# SCH___2022-10-18.net
KiCad netlist of a schematic drawn in EasyEDA
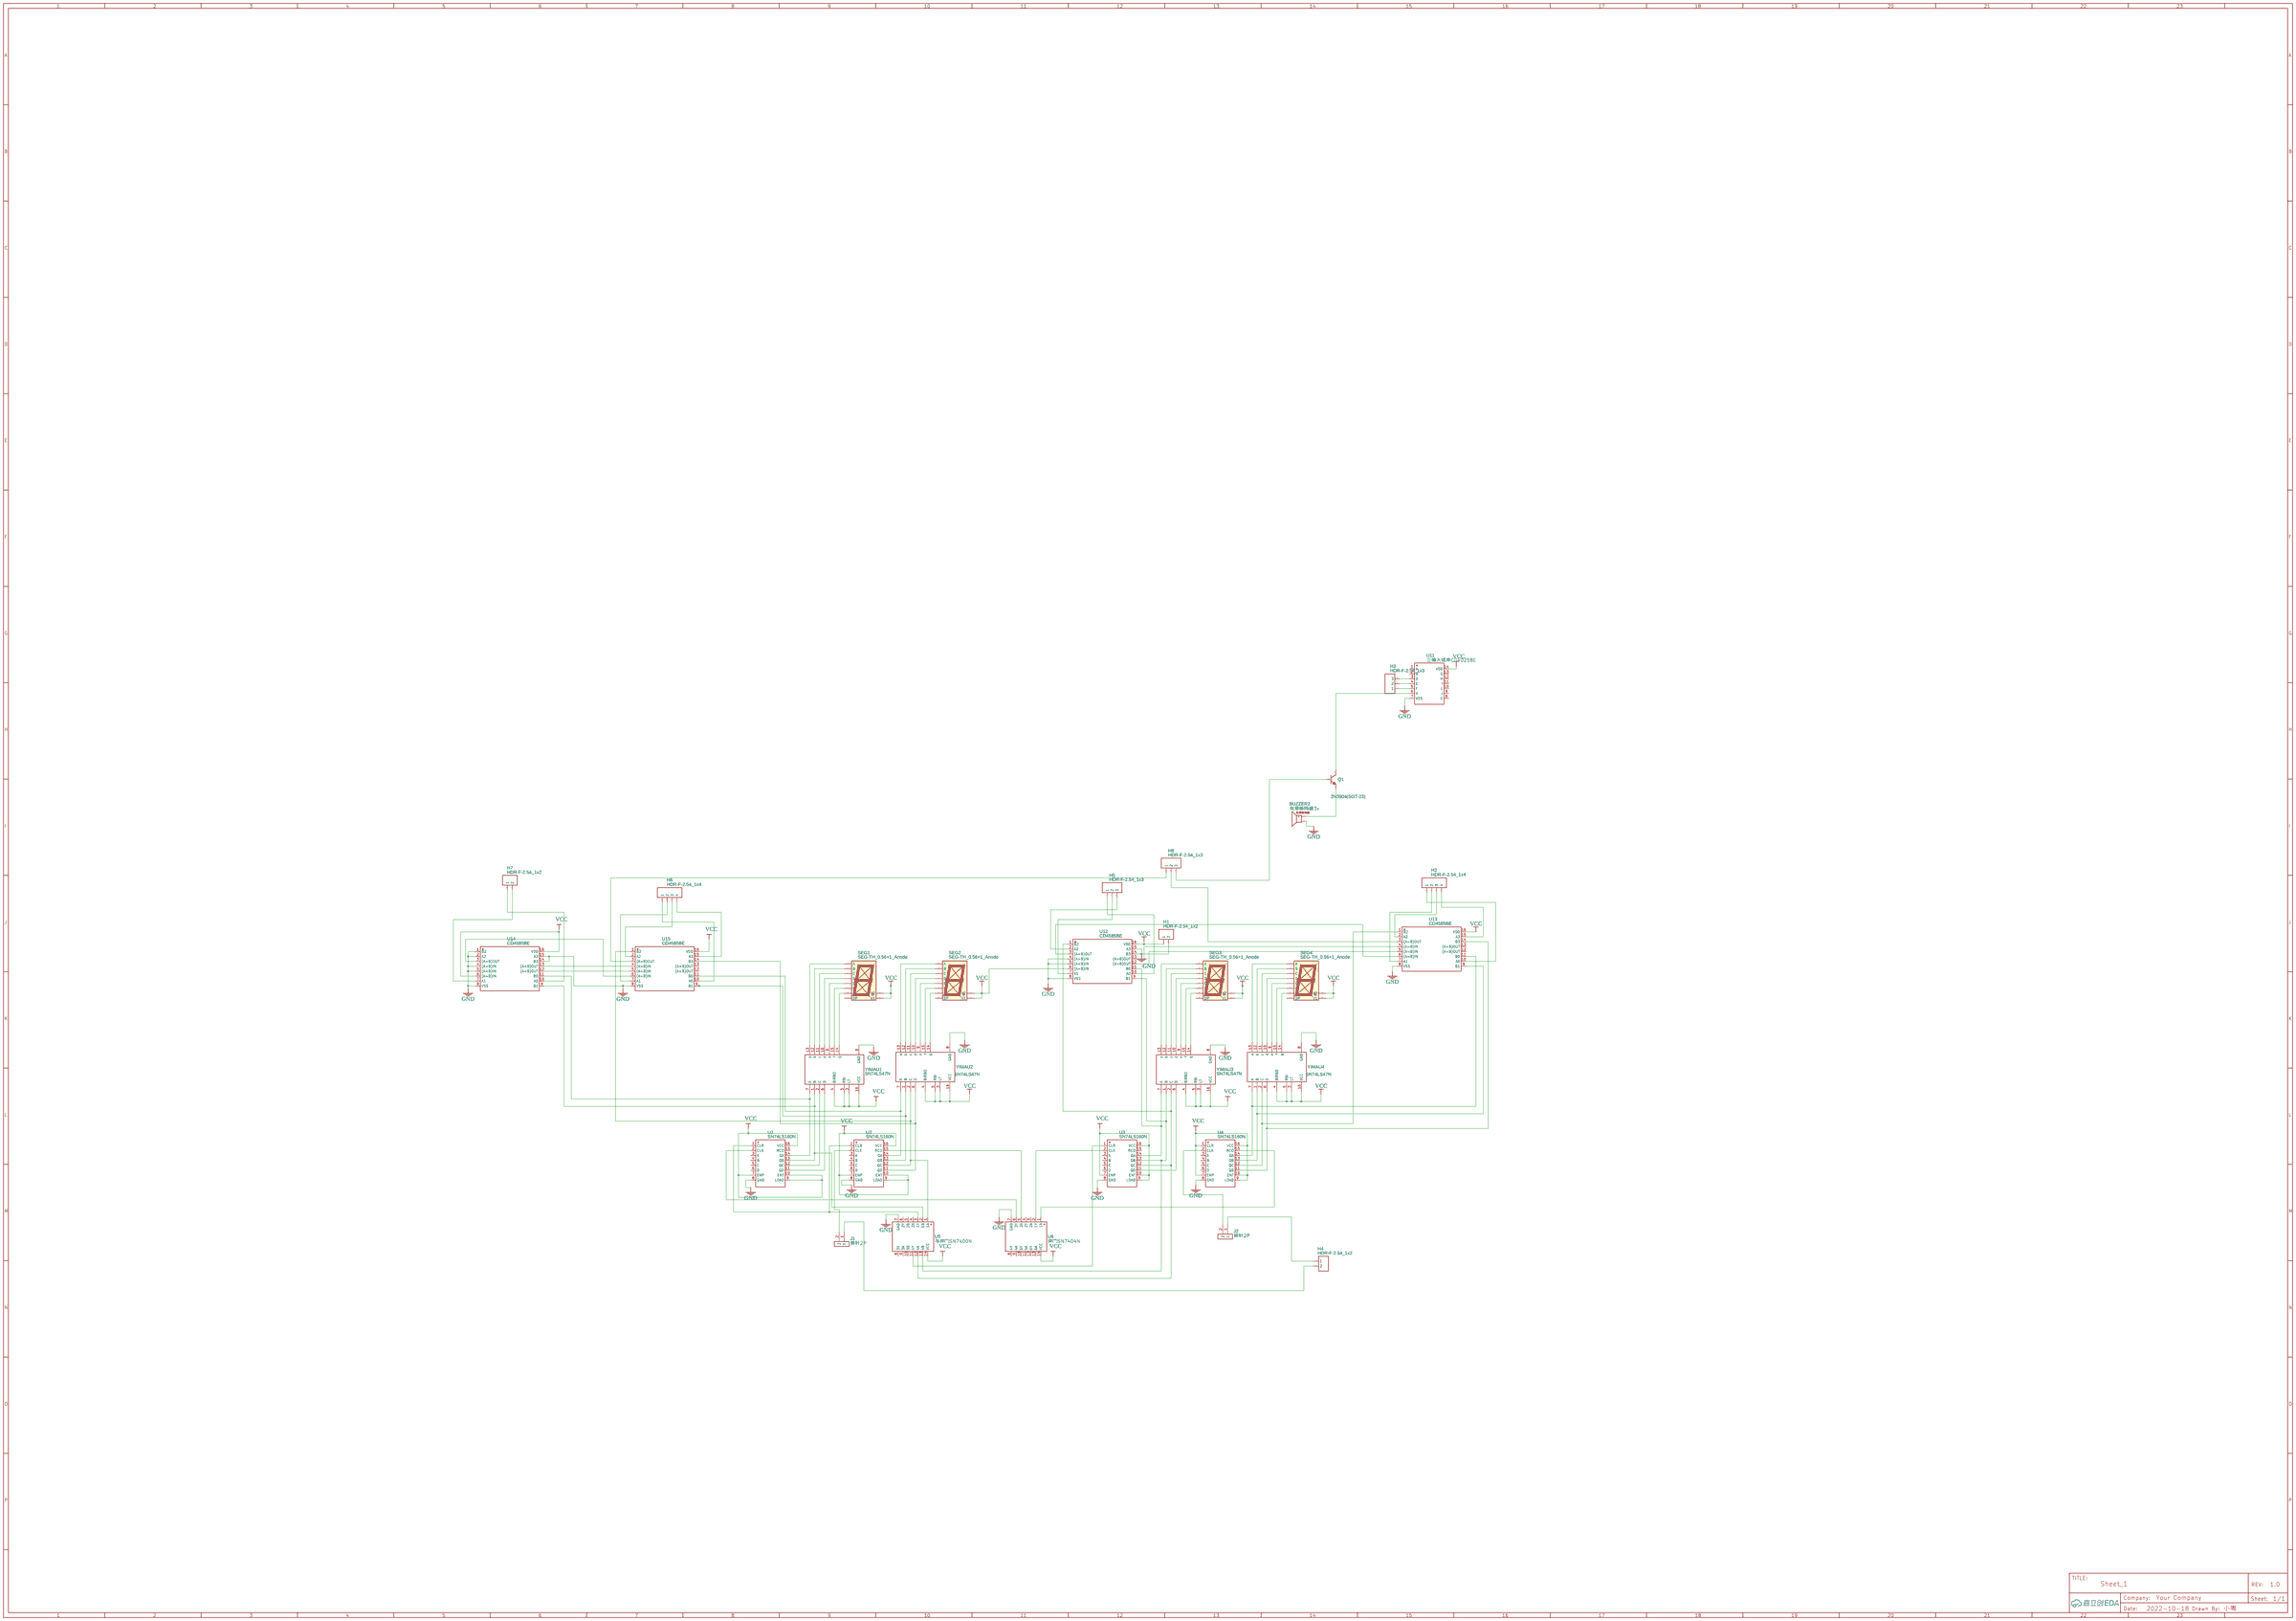
[diagram p0: schematic sheet]

(export (version "E")
  (design (tool "Eeschema 10.0.6"))
  (components
    (comp (ref "BUZZER2")
      (value "有源蜂鸣器3v")
      (fields (field (name "BOM_Manufacturer Part") "TMB12A12") (field (name "BOM_Supplier Part") "C96079"))
      (libsource (lib "") (part "有源蜂鸣器3v"))
    )
    (comp (ref "H1")
      (value "HDR-F-2.54_1x2")
      (fields (field (name "BOM_Supplier Part") "C49661"))
      (libsource (lib "") (part "HDR-F-2.54_1x2"))
    )
    (comp (ref "H2")
      (value "HDR-F-2.54_1x4")
      (fields (field (name "BOM_Supplier Part") "C225501"))
      (libsource (lib "") (part "HDR-F-2.54_1x4"))
    )
    (comp (ref "H3")
      (value "HDR-F-2.54_1x3")
      (fields (field (name "BOM_Supplier Part") "C146690"))
      (libsource (lib "") (part "HDR-F-2.54_1x3_1"))
    )
    (comp (ref "H4")
      (value "HDR-F-2.54_1x2")
      (fields (field (name "BOM_Supplier Part") "C49661"))
      (libsource (lib "") (part "HDR-F-2.54_1x2_1"))
    )
    (comp (ref "H5")
      (value "HDR-F-2.54_1x3")
      (fields (field (name "BOM_Supplier Part") "C146690"))
      (libsource (lib "") (part "HDR-F-2.54_1x3"))
    )
    (comp (ref "H6")
      (value "HDR-F-2.54_1x4")
      (fields (field (name "BOM_Supplier Part") "C225501"))
      (libsource (lib "") (part "HDR-F-2.54_1x4"))
    )
    (comp (ref "H7")
      (value "HDR-F-2.54_1x2")
      (fields (field (name "BOM_Supplier Part") "C49661"))
      (libsource (lib "") (part "HDR-F-2.54_1x2"))
    )
    (comp (ref "H8")
      (value "HDR-F-2.54_1x3")
      (fields (field (name "BOM_Supplier Part") "C146690"))
      (libsource (lib "") (part "HDR-F-2.54_1x3"))
    )
    (comp (ref "J1") (value "排针2P") (libsource (lib "") (part "排针2P")))
    (comp (ref "J2") (value "排针2P") (libsource (lib "") (part "排针2P")))
    (comp (ref "Q1")
      (value "2N3904(SOT-23)")
      (fields
        (field (name "BOM_Manufacturer Part") "2n3904S-RTK/PS")
        (field (name "BOM_Supplier Part") "C18536")
      )
      (libsource (lib "") (part "2N3904(SOT-23)"))
    )
    (comp (ref "SEG1")
      (value "SEG-TH_0.56×1_Anode")
      (fields (field (name "BOM_Supplier Part") "C8092"))
      (libsource (lib "") (part "SEG-TH_0.56×1_Anode"))
    )
    (comp (ref "SEG2")
      (value "SEG-TH_0.56×1_Anode")
      (fields (field (name "BOM_Supplier Part") "C8092"))
      (libsource (lib "") (part "SEG-TH_0.56×1_Anode"))
    )
    (comp (ref "SEG3")
      (value "SEG-TH_0.56×1_Anode")
      (fields (field (name "BOM_Supplier Part") "C8092"))
      (libsource (lib "") (part "SEG-TH_0.56×1_Anode"))
    )
    (comp (ref "SEG4")
      (value "SEG-TH_0.56×1_Anode")
      (fields (field (name "BOM_Supplier Part") "C8092"))
      (libsource (lib "") (part "SEG-TH_0.56×1_Anode"))
    )
    (comp (ref "U1")
      (value "SN74LS160N")
      (fields
        (field (name "BOM_Manufacturer Part") "CC0805JRNPO9BN821")
        (field (name "BOM_Supplier Part") "C113834")
      )
      (libsource (lib "") (part "SN74LS160N"))
    )
    (comp (ref "U2")
      (value "SN74LS160N")
      (fields
        (field (name "BOM_Manufacturer Part") "CC0805JRNPO9BN821")
        (field (name "BOM_Supplier Part") "C113834")
      )
      (libsource (lib "") (part "SN74LS160N"))
    )
    (comp (ref "U3")
      (value "SN74LS160N")
      (fields
        (field (name "BOM_Manufacturer Part") "CC0805JRNPO9BN821")
        (field (name "BOM_Supplier Part") "C113834")
      )
      (libsource (lib "") (part "SN74LS160N"))
    )
    (comp (ref "U4")
      (value "SN74LS160N")
      (fields
        (field (name "BOM_Manufacturer Part") "CC0805JRNPO9BN821")
        (field (name "BOM_Supplier Part") "C113834")
      )
      (libsource (lib "") (part "SN74LS160N"))
    )
    (comp (ref "U5") (value "与非门SN7400N") (libsource (lib "") (part "SN7400N")))
    (comp (ref "U6") (value "非门SN7404N") (libsource (lib "") (part "SN7404N")))
    (comp (ref "U11")
      (value "三输入或非CD4025BE")
      (fields (field (name "BOM_Manufacturer Part") "CD4025BE") (field (name "BOM_Supplier Part") "C28214"))
      (libsource (lib "") (part "CD4025BE"))
    )
    (comp (ref "U12")
      (value "CD4585BE")
      (fields (field (name "BOM_Supplier Part") "C31466"))
      (libsource (lib "") (part "CD4585BE"))
    )
    (comp (ref "U13")
      (value "CD4585BE")
      (fields (field (name "BOM_Supplier Part") "C31466"))
      (libsource (lib "") (part "CD4585BE"))
    )
    (comp (ref "U14")
      (value "CD4585BE")
      (fields (field (name "BOM_Supplier Part") "C31466"))
      (libsource (lib "") (part "CD4585BE"))
    )
    (comp (ref "U15")
      (value "CD4585BE")
      (fields (field (name "BOM_Supplier Part") "C31466"))
      (libsource (lib "") (part "CD4585BE"))
    )
    (comp (ref "YIMAU1")
      (value "SN74LS47N")
      (fields (field (name "BOM_Supplier Part") "C129379"))
      (libsource (lib "") (part "Unknown_1690_-1115"))
    )
    (comp (ref "YIMAU2")
      (value "SN74LS47N")
      (fields (field (name "BOM_Supplier Part") "C129379"))
      (libsource (lib "") (part "Unknown_1875_-1120"))
    )
    (comp (ref "YIMAU3")
      (value "SN74LS47N")
      (fields (field (name "BOM_Supplier Part") "C129379"))
      (libsource (lib "") (part "Unknown_2405_-1115"))
    )
    (comp (ref "YIMAU4")
      (value "SN74LS47N")
      (fields (field (name "BOM_Supplier Part") "C129379"))
      (libsource (lib "") (part "Unknown_2590_-1120"))
    )
  )
  (nets
    (net (code "1") (name "GND") (class "Default")
      (node (ref "BUZZER2") (pin "-") (pinfunction "-_-") (pintype "unspecified"))
      (node (ref "H1") (pin "2") (pinfunction "2_2") (pintype "input"))
      (node (ref "U1") (pin "8") (pinfunction "GND_8") (pintype "unspecified"))
      (node (ref "U11") (pin "7") (pinfunction "VSS_7") (pintype "unspecified"))
      (node (ref "U12") (pin "14") (pinfunction "B3_14") (pintype "unspecified"))
      (node (ref "U12") (pin "15") (pinfunction "A3_15") (pintype "unspecified"))
      (node (ref "U12") (pin "4") (pinfunction "(A>B)IN_4") (pintype "unspecified"))
      (node (ref "U12") (pin "5") (pinfunction "(A<B)IN_5") (pintype "unspecified"))
      (node (ref "U12") (pin "8") (pinfunction "VSS_8") (pintype "unspecified"))
      (node (ref "U13") (pin "8") (pinfunction "VSS_8") (pintype "unspecified"))
      (node (ref "U14") (pin "1") (pinfunction "B2_1") (pintype "unspecified"))
      (node (ref "U14") (pin "14") (pinfunction "B3_14") (pintype "unspecified"))
      (node (ref "U14") (pin "15") (pinfunction "A3_15") (pintype "unspecified"))
      (node (ref "U14") (pin "2") (pinfunction "A2_2") (pintype "unspecified"))
      (node (ref "U14") (pin "4") (pinfunction "(A>B)IN_4") (pintype "unspecified"))
      (node (ref "U14") (pin "5") (pinfunction "(A<B)IN_5") (pintype "unspecified"))
      (node (ref "U14") (pin "8") (pinfunction "VSS_8") (pintype "unspecified"))
      (node (ref "U15") (pin "8") (pinfunction "VSS_8") (pintype "unspecified"))
      (node (ref "U2") (pin "8") (pinfunction "GND_8") (pintype "unspecified"))
      (node (ref "U3") (pin "8") (pinfunction "GND_8") (pintype "unspecified"))
      (node (ref "U4") (pin "8") (pinfunction "GND_8") (pintype "unspecified"))
      (node (ref "U5") (pin "7") (pinfunction "GND_7") (pintype "unspecified"))
      (node (ref "U6") (pin "7") (pinfunction "GND_7") (pintype "unspecified"))
      (node (ref "YIMAU1") (pin "8") (pinfunction "GND_8") (pintype "passive"))
      (node (ref "YIMAU2") (pin "8") (pinfunction "GND_8") (pintype "passive"))
      (node (ref "YIMAU3") (pin "8") (pinfunction "GND_8") (pintype "passive"))
      (node (ref "YIMAU4") (pin "8") (pinfunction "GND_8") (pintype "passive"))
    )
    (net (code "2") (name "Net-(H4-Pad1)") (class "Default")
      (node (ref "H4") (pin "1") (pinfunction "1_1") (pintype "input"))
      (node (ref "J2") (pin "1") (pinfunction "1_1") (pintype "unspecified"))
    )
    (net (code "3") (name "Net-(H4-Pad2)") (class "Default")
      (node (ref "H4") (pin "2") (pinfunction "2_2") (pintype "input"))
      (node (ref "J1") (pin "1") (pinfunction "1_1") (pintype "unspecified"))
    )
    (net (code "4") (name "Net-(Q1-B)") (class "Default")
      (node (ref "H8") (pin "3") (pinfunction "3_3") (pintype "input"))
      (node (ref "Q1") (pin "2") (pinfunction "B_2") (pintype "input"))
    )
    (net (code "5") (name "Net-(Q1-C)") (class "Default")
      (node (ref "Q1") (pin "3") (pinfunction "C_3") (pintype "input"))
      (node (ref "U11") (pin "6") (pinfunction "K_6") (pintype "unspecified"))
    )
    (net (code "6") (name "Net-(Q1-E)") (class "Default")
      (node (ref "BUZZER2") (pin "+") (pinfunction "+_+") (pintype "unspecified"))
      (node (ref "Q1") (pin "1") (pinfunction "E_1") (pintype "input"))
    )
    (net (code "7") (name "Net-(SEG1-A)") (class "Default")
      (node (ref "SEG1") (pin "7") (pinfunction "A_7") (pintype "unspecified"))
      (node (ref "YIMAU1") (pin "13") (pinfunction "a_13") (pintype "unspecified"))
    )
    (net (code "8") (name "Net-(SEG1-B)") (class "Default")
      (node (ref "SEG1") (pin "6") (pinfunction "B_6") (pintype "unspecified"))
      (node (ref "YIMAU1") (pin "12") (pinfunction "b_12") (pintype "unspecified"))
    )
    (net (code "9") (name "Net-(SEG1-C)") (class "Default")
      (node (ref "SEG1") (pin "4") (pinfunction "C_4") (pintype "unspecified"))
      (node (ref "YIMAU1") (pin "11") (pinfunction "c_11") (pintype "unspecified"))
    )
    (net (code "10") (name "Net-(SEG1-D)") (class "Default")
      (node (ref "SEG1") (pin "2") (pinfunction "D_2") (pintype "unspecified"))
      (node (ref "YIMAU1") (pin "10") (pinfunction "d_10") (pintype "unspecified"))
    )
    (net (code "11") (name "Net-(SEG1-E)") (class "Default")
      (node (ref "SEG1") (pin "1") (pinfunction "E_1") (pintype "unspecified"))
      (node (ref "YIMAU1") (pin "9") (pinfunction "e_9") (pintype "unspecified"))
    )
    (net (code "12") (name "Net-(SEG1-F)") (class "Default")
      (node (ref "SEG1") (pin "9") (pinfunction "F_9") (pintype "unspecified"))
      (node (ref "YIMAU1") (pin "15") (pinfunction "f_15") (pintype "unspecified"))
    )
    (net (code "13") (name "Net-(SEG1-G)") (class "Default")
      (node (ref "SEG1") (pin "10") (pinfunction "G_10") (pintype "unspecified"))
      (node (ref "YIMAU1") (pin "14") (pinfunction "g_14") (pintype "unspecified"))
    )
    (net (code "14") (name "Net-(SEG2-A)") (class "Default")
      (node (ref "SEG2") (pin "7") (pinfunction "A_7") (pintype "unspecified"))
      (node (ref "YIMAU2") (pin "13") (pinfunction "a_13") (pintype "unspecified"))
    )
    (net (code "15") (name "Net-(SEG2-B)") (class "Default")
      (node (ref "SEG2") (pin "6") (pinfunction "B_6") (pintype "unspecified"))
      (node (ref "YIMAU2") (pin "12") (pinfunction "b_12") (pintype "unspecified"))
    )
    (net (code "16") (name "Net-(SEG2-C)") (class "Default")
      (node (ref "SEG2") (pin "4") (pinfunction "C_4") (pintype "unspecified"))
      (node (ref "YIMAU2") (pin "11") (pinfunction "c_11") (pintype "unspecified"))
    )
    (net (code "17") (name "Net-(SEG2-D)") (class "Default")
      (node (ref "SEG2") (pin "2") (pinfunction "D_2") (pintype "unspecified"))
      (node (ref "YIMAU2") (pin "10") (pinfunction "d_10") (pintype "unspecified"))
    )
    (net (code "18") (name "Net-(SEG2-E)") (class "Default")
      (node (ref "SEG2") (pin "1") (pinfunction "E_1") (pintype "unspecified"))
      (node (ref "YIMAU2") (pin "9") (pinfunction "e_9") (pintype "unspecified"))
    )
    (net (code "19") (name "Net-(SEG2-F)") (class "Default")
      (node (ref "SEG2") (pin "9") (pinfunction "F_9") (pintype "unspecified"))
      (node (ref "YIMAU2") (pin "15") (pinfunction "f_15") (pintype "unspecified"))
    )
    (net (code "20") (name "Net-(SEG2-G)") (class "Default")
      (node (ref "SEG2") (pin "10") (pinfunction "G_10") (pintype "unspecified"))
      (node (ref "YIMAU2") (pin "14") (pinfunction "g_14") (pintype "unspecified"))
    )
    (net (code "21") (name "Net-(SEG3-A)") (class "Default")
      (node (ref "SEG3") (pin "7") (pinfunction "A_7") (pintype "unspecified"))
      (node (ref "YIMAU3") (pin "13") (pinfunction "a_13") (pintype "unspecified"))
    )
    (net (code "22") (name "Net-(SEG3-B)") (class "Default")
      (node (ref "SEG3") (pin "6") (pinfunction "B_6") (pintype "unspecified"))
      (node (ref "YIMAU3") (pin "12") (pinfunction "b_12") (pintype "unspecified"))
    )
    (net (code "23") (name "Net-(SEG3-C)") (class "Default")
      (node (ref "SEG3") (pin "4") (pinfunction "C_4") (pintype "unspecified"))
      (node (ref "YIMAU3") (pin "11") (pinfunction "c_11") (pintype "unspecified"))
    )
    (net (code "24") (name "Net-(SEG3-D)") (class "Default")
      (node (ref "SEG3") (pin "2") (pinfunction "D_2") (pintype "unspecified"))
      (node (ref "YIMAU3") (pin "10") (pinfunction "d_10") (pintype "unspecified"))
    )
    (net (code "25") (name "Net-(SEG3-E)") (class "Default")
      (node (ref "SEG3") (pin "1") (pinfunction "E_1") (pintype "unspecified"))
      (node (ref "YIMAU3") (pin "9") (pinfunction "e_9") (pintype "unspecified"))
    )
    (net (code "26") (name "Net-(SEG3-F)") (class "Default")
      (node (ref "SEG3") (pin "9") (pinfunction "F_9") (pintype "unspecified"))
      (node (ref "YIMAU3") (pin "15") (pinfunction "f_15") (pintype "unspecified"))
    )
    (net (code "27") (name "Net-(SEG3-G)") (class "Default")
      (node (ref "SEG3") (pin "10") (pinfunction "G_10") (pintype "unspecified"))
      (node (ref "YIMAU3") (pin "14") (pinfunction "g_14") (pintype "unspecified"))
    )
    (net (code "28") (name "Net-(SEG4-A)") (class "Default")
      (node (ref "SEG4") (pin "7") (pinfunction "A_7") (pintype "unspecified"))
      (node (ref "YIMAU4") (pin "13") (pinfunction "a_13") (pintype "unspecified"))
    )
    (net (code "29") (name "Net-(SEG4-B)") (class "Default")
      (node (ref "SEG4") (pin "6") (pinfunction "B_6") (pintype "unspecified"))
      (node (ref "YIMAU4") (pin "12") (pinfunction "b_12") (pintype "unspecified"))
    )
    (net (code "30") (name "Net-(SEG4-C)") (class "Default")
      (node (ref "SEG4") (pin "4") (pinfunction "C_4") (pintype "unspecified"))
      (node (ref "YIMAU4") (pin "11") (pinfunction "c_11") (pintype "unspecified"))
    )
    (net (code "31") (name "Net-(SEG4-D)") (class "Default")
      (node (ref "SEG4") (pin "2") (pinfunction "D_2") (pintype "unspecified"))
      (node (ref "YIMAU4") (pin "10") (pinfunction "d_10") (pintype "unspecified"))
    )
    (net (code "32") (name "Net-(SEG4-E)") (class "Default")
      (node (ref "SEG4") (pin "1") (pinfunction "E_1") (pintype "unspecified"))
      (node (ref "YIMAU4") (pin "9") (pinfunction "e_9") (pintype "unspecified"))
    )
    (net (code "33") (name "Net-(SEG4-F)") (class "Default")
      (node (ref "SEG4") (pin "9") (pinfunction "F_9") (pintype "unspecified"))
      (node (ref "YIMAU4") (pin "15") (pinfunction "f_15") (pintype "unspecified"))
    )
    (net (code "34") (name "Net-(SEG4-G)") (class "Default")
      (node (ref "SEG4") (pin "10") (pinfunction "G_10") (pintype "unspecified"))
      (node (ref "YIMAU4") (pin "14") (pinfunction "g_14") (pintype "unspecified"))
    )
    (net (code "35") (name "Net-(U1-CLK)") (class "Default")
      (node (ref "U1") (pin "2") (pinfunction "CLK_2") (pintype "unspecified"))
      (node (ref "U6") (pin "6") (pinfunction "3Y_6") (pintype "unspecified"))
    )
    (net (code "36") (name "Net-(U1-CLR)") (class "Default")
      (node (ref "U1") (pin "1") (pinfunction "CLR_1") (pintype "unspecified"))
      (node (ref "U2") (pin "1") (pinfunction "CLR_1") (pintype "unspecified"))
      (node (ref "U5") (pin "3") (pinfunction "1Y_3") (pintype "unspecified"))
    )
    (net (code "37") (name "Net-(U1-QA)") (class "Default")
      (node (ref "U1") (pin "14") (pinfunction "QA_14") (pintype "unspecified"))
      (node (ref "U14") (pin "11") (pinfunction "B0_11") (pintype "unspecified"))
      (node (ref "YIMAU1") (pin "7") (pinfunction "A_7") (pintype "unspecified"))
    )
    (net (code "38") (name "Net-(U1-QB)") (class "Default")
      (node (ref "U1") (pin "13") (pinfunction "QB_13") (pintype "unspecified"))
      (node (ref "U14") (pin "9") (pinfunction "B1_9") (pintype "unspecified"))
      (node (ref "U5") (pin "2") (pinfunction "1B_2") (pintype "unspecified"))
      (node (ref "YIMAU1") (pin "1") (pinfunction "B_1") (pintype "unspecified"))
    )
    (net (code "39") (name "Net-(U1-QC)") (class "Default")
      (node (ref "U1") (pin "12") (pinfunction "QC_12") (pintype "unspecified"))
      (node (ref "YIMAU1") (pin "2") (pinfunction "C_2") (pintype "unspecified"))
    )
    (net (code "40") (name "Net-(U1-QD)") (class "Default")
      (node (ref "U1") (pin "11") (pinfunction "QD_11") (pintype "unspecified"))
      (node (ref "YIMAU1") (pin "6") (pinfunction "D_6") (pintype "unspecified"))
    )
    (net (code "41") (name "Net-(U2-CLK)") (class "Default")
      (node (ref "J1") (pin "2") (pinfunction "2_2") (pintype "unspecified"))
      (node (ref "U2") (pin "2") (pinfunction "CLK_2") (pintype "unspecified"))
    )
    (net (code "42") (name "Net-(U2-RCO)") (class "Default")
      (node (ref "U2") (pin "15") (pinfunction "RCO_15") (pintype "unspecified"))
      (node (ref "U6") (pin "5") (pinfunction "3A_5") (pintype "unspecified"))
    )
    (net (code "43") (name "Net-(U3-CLK)") (class "Default")
      (node (ref "U3") (pin "2") (pinfunction "CLK_2") (pintype "unspecified"))
      (node (ref "U6") (pin "2") (pinfunction "1Y_2") (pintype "unspecified"))
    )
    (net (code "44") (name "Net-(U3-CLR)") (class "Default")
      (node (ref "U3") (pin "1") (pinfunction "CLR_1") (pintype "unspecified"))
      (node (ref "U5") (pin "11") (pinfunction "4Y_11") (pintype "unspecified"))
    )
    (net (code "45") (name "Net-(U3-QD)") (class "Default")
      (node (ref "U3") (pin "11") (pinfunction "QD_11") (pintype "unspecified"))
      (node (ref "YIMAU3") (pin "6") (pinfunction "D_6") (pintype "unspecified"))
    )
    (net (code "46") (name "Net-(U4-CLK)") (class "Default")
      (node (ref "J2") (pin "2") (pinfunction "2_2") (pintype "unspecified"))
      (node (ref "U4") (pin "2") (pinfunction "CLK_2") (pintype "unspecified"))
    )
    (net (code "47") (name "Net-(U4-RCO)") (class "Default")
      (node (ref "U4") (pin "15") (pinfunction "RCO_15") (pintype "unspecified"))
      (node (ref "U6") (pin "1") (pinfunction "1A_1") (pintype "unspecified"))
    )
    (net (code "48") (name "Net-(U11-D)") (class "Default")
      (node (ref "H3") (pin "3") (pinfunction "3_3") (pintype "input"))
      (node (ref "U11") (pin "3") (pinfunction "D_3") (pintype "unspecified"))
    )
    (net (code "49") (name "Net-(U11-E)") (class "Default")
      (node (ref "H3") (pin "2") (pinfunction "2_2") (pintype "input"))
      (node (ref "U11") (pin "4") (pinfunction "E_4") (pintype "unspecified"))
    )
    (net (code "50") (name "Net-(U11-F)") (class "Default")
      (node (ref "H3") (pin "1") (pinfunction "1_1") (pintype "input"))
      (node (ref "U11") (pin "5") (pinfunction "F_5") (pintype "unspecified"))
    )
    (net (code "51") (name "Net-(U12-(A<B)OUT)") (class "Default")
      (node (ref "U12") (pin "12") (pinfunction "(A<B)OUT_12") (pintype "unspecified"))
      (node (ref "U13") (pin "5") (pinfunction "(A<B)IN_5") (pintype "unspecified"))
    )
    (net (code "52") (name "Net-(U12-(A=B)OUT)") (class "Default")
      (node (ref "U12") (pin "3") (pinfunction "(A=B)OUT_3") (pintype "unspecified"))
      (node (ref "U13") (pin "6") (pinfunction "(A=B)IN_6") (pintype "unspecified"))
    )
    (net (code "53") (name "Net-(U12-(A>B)OUT)") (class "Default")
      (node (ref "U12") (pin "13") (pinfunction "(A>B)OUT_13") (pintype "unspecified"))
      (node (ref "U13") (pin "4") (pinfunction "(A>B)IN_4") (pintype "unspecified"))
    )
    (net (code "54") (name "Net-(U12-A0)") (class "Default")
      (node (ref "H5") (pin "1") (pinfunction "1_1") (pintype "input"))
      (node (ref "U12") (pin "10") (pinfunction "A0_10") (pintype "unspecified"))
    )
    (net (code "55") (name "Net-(U12-A1)") (class "Default")
      (node (ref "H5") (pin "2") (pinfunction "2_2") (pintype "input"))
      (node (ref "U12") (pin "7") (pinfunction "A1_7") (pintype "unspecified"))
    )
    (net (code "56") (name "Net-(U12-A2)") (class "Default")
      (node (ref "H5") (pin "3") (pinfunction "3_3") (pintype "input"))
      (node (ref "U12") (pin "2") (pinfunction "A2_2") (pintype "unspecified"))
    )
    (net (code "57") (name "Net-(U12-B0)") (class "Default")
      (node (ref "U12") (pin "11") (pinfunction "B0_11") (pintype "unspecified"))
      (node (ref "U3") (pin "14") (pinfunction "QA_14") (pintype "unspecified"))
      (node (ref "YIMAU3") (pin "7") (pinfunction "A_7") (pintype "unspecified"))
    )
    (net (code "58") (name "Net-(U12-B1)") (class "Default")
      (node (ref "U12") (pin "9") (pinfunction "B1_9") (pintype "unspecified"))
      (node (ref "U3") (pin "13") (pinfunction "QB_13") (pintype "unspecified"))
      (node (ref "U5") (pin "13") (pinfunction "4B_13") (pintype "unspecified"))
      (node (ref "YIMAU3") (pin "1") (pinfunction "B_1") (pintype "unspecified"))
    )
    (net (code "59") (name "Net-(U12-B2)") (class "Default")
      (node (ref "U12") (pin "1") (pinfunction "B2_1") (pintype "unspecified"))
      (node (ref "U3") (pin "12") (pinfunction "QC_12") (pintype "unspecified"))
      (node (ref "U5") (pin "12") (pinfunction "4A_12") (pintype "unspecified"))
      (node (ref "YIMAU3") (pin "2") (pinfunction "C_2") (pintype "unspecified"))
    )
    (net (code "60") (name "Net-(U13-(A=B)OUT)") (class "Default")
      (node (ref "H8") (pin "2") (pinfunction "2_2") (pintype "input"))
      (node (ref "U13") (pin "3") (pinfunction "(A=B)OUT_3") (pintype "unspecified"))
    )
    (net (code "61") (name "Net-(U13-A0)") (class "Default")
      (node (ref "H2") (pin "1") (pinfunction "1_1") (pintype "unspecified"))
      (node (ref "U13") (pin "10") (pinfunction "A0_10") (pintype "unspecified"))
    )
    (net (code "62") (name "Net-(U13-A1)") (class "Default")
      (node (ref "H2") (pin "2") (pinfunction "2_2") (pintype "unspecified"))
      (node (ref "U13") (pin "7") (pinfunction "A1_7") (pintype "unspecified"))
    )
    (net (code "63") (name "Net-(U13-A2)") (class "Default")
      (node (ref "H2") (pin "3") (pinfunction "3_3") (pintype "unspecified"))
      (node (ref "U13") (pin "2") (pinfunction "A2_2") (pintype "unspecified"))
    )
    (net (code "64") (name "Net-(U13-A3)") (class "Default")
      (node (ref "H2") (pin "4") (pinfunction "4_4") (pintype "unspecified"))
      (node (ref "U13") (pin "15") (pinfunction "A3_15") (pintype "unspecified"))
    )
    (net (code "65") (name "Net-(U13-B0)") (class "Default")
      (node (ref "U13") (pin "11") (pinfunction "B0_11") (pintype "unspecified"))
      (node (ref "U4") (pin "14") (pinfunction "QA_14") (pintype "unspecified"))
      (node (ref "YIMAU4") (pin "7") (pinfunction "A_7") (pintype "unspecified"))
    )
    (net (code "66") (name "Net-(U13-B1)") (class "Default")
      (node (ref "U13") (pin "9") (pinfunction "B1_9") (pintype "unspecified"))
      (node (ref "U4") (pin "13") (pinfunction "QB_13") (pintype "unspecified"))
      (node (ref "YIMAU4") (pin "1") (pinfunction "B_1") (pintype "unspecified"))
    )
    (net (code "67") (name "Net-(U13-B2)") (class "Default")
      (node (ref "U13") (pin "1") (pinfunction "B2_1") (pintype "unspecified"))
      (node (ref "U4") (pin "12") (pinfunction "QC_12") (pintype "unspecified"))
      (node (ref "YIMAU4") (pin "2") (pinfunction "C_2") (pintype "unspecified"))
    )
    (net (code "68") (name "Net-(U13-B3)") (class "Default")
      (node (ref "U13") (pin "14") (pinfunction "B3_14") (pintype "unspecified"))
      (node (ref "U4") (pin "11") (pinfunction "QD_11") (pintype "unspecified"))
      (node (ref "YIMAU4") (pin "6") (pinfunction "D_6") (pintype "unspecified"))
    )
    (net (code "69") (name "Net-(U14-(A<B)OUT)") (class "Default")
      (node (ref "U14") (pin "12") (pinfunction "(A<B)OUT_12") (pintype "unspecified"))
      (node (ref "U15") (pin "5") (pinfunction "(A<B)IN_5") (pintype "unspecified"))
    )
    (net (code "70") (name "Net-(U14-(A=B)OUT)") (class "Default")
      (node (ref "U14") (pin "3") (pinfunction "(A=B)OUT_3") (pintype "unspecified"))
      (node (ref "U15") (pin "6") (pinfunction "(A=B)IN_6") (pintype "unspecified"))
    )
    (net (code "71") (name "Net-(U14-(A>B)OUT)") (class "Default")
      (node (ref "U14") (pin "13") (pinfunction "(A>B)OUT_13") (pintype "unspecified"))
      (node (ref "U15") (pin "4") (pinfunction "(A>B)IN_4") (pintype "unspecified"))
    )
    (net (code "72") (name "Net-(U14-A0)") (class "Default")
      (node (ref "H7") (pin "1") (pinfunction "1_1") (pintype "input"))
      (node (ref "U14") (pin "10") (pinfunction "A0_10") (pintype "unspecified"))
    )
    (net (code "73") (name "Net-(U14-A1)") (class "Default")
      (node (ref "H7") (pin "2") (pinfunction "2_2") (pintype "input"))
      (node (ref "U14") (pin "7") (pinfunction "A1_7") (pintype "unspecified"))
    )
    (net (code "74") (name "Net-(U15-(A=B)OUT)") (class "Default")
      (node (ref "H8") (pin "1") (pinfunction "1_1") (pintype "input"))
      (node (ref "U15") (pin "3") (pinfunction "(A=B)OUT_3") (pintype "unspecified"))
    )
    (net (code "75") (name "Net-(U15-A0)") (class "Default")
      (node (ref "H6") (pin "1") (pinfunction "1_1") (pintype "unspecified"))
      (node (ref "U15") (pin "10") (pinfunction "A0_10") (pintype "unspecified"))
    )
    (net (code "76") (name "Net-(U15-A1)") (class "Default")
      (node (ref "H6") (pin "2") (pinfunction "2_2") (pintype "unspecified"))
      (node (ref "U15") (pin "7") (pinfunction "A1_7") (pintype "unspecified"))
    )
    (net (code "77") (name "Net-(U15-A2)") (class "Default")
      (node (ref "H6") (pin "3") (pinfunction "3_3") (pintype "unspecified"))
      (node (ref "U15") (pin "2") (pinfunction "A2_2") (pintype "unspecified"))
    )
    (net (code "78") (name "Net-(U15-A3)") (class "Default")
      (node (ref "H6") (pin "4") (pinfunction "4_4") (pintype "unspecified"))
      (node (ref "U15") (pin "15") (pinfunction "A3_15") (pintype "unspecified"))
    )
    (net (code "79") (name "Net-(U15-B0)") (class "Default")
      (node (ref "U15") (pin "11") (pinfunction "B0_11") (pintype "unspecified"))
      (node (ref "U2") (pin "14") (pinfunction "QA_14") (pintype "unspecified"))
      (node (ref "YIMAU2") (pin "7") (pinfunction "A_7") (pintype "unspecified"))
    )
    (net (code "80") (name "Net-(U15-B1)") (class "Default")
      (node (ref "U15") (pin "9") (pinfunction "B1_9") (pintype "unspecified"))
      (node (ref "U2") (pin "13") (pinfunction "QB_13") (pintype "unspecified"))
      (node (ref "YIMAU2") (pin "1") (pinfunction "B_1") (pintype "unspecified"))
    )
    (net (code "81") (name "Net-(U15-B2)") (class "Default")
      (node (ref "U15") (pin "1") (pinfunction "B2_1") (pintype "unspecified"))
      (node (ref "U2") (pin "12") (pinfunction "QC_12") (pintype "unspecified"))
      (node (ref "U5") (pin "1") (pinfunction "1A_1") (pintype "unspecified"))
      (node (ref "YIMAU2") (pin "2") (pinfunction "C_2") (pintype "unspecified"))
    )
    (net (code "82") (name "Net-(U15-B3)") (class "Default")
      (node (ref "U15") (pin "14") (pinfunction "B3_14") (pintype "unspecified"))
      (node (ref "U2") (pin "11") (pinfunction "QD_11") (pintype "unspecified"))
      (node (ref "YIMAU2") (pin "6") (pinfunction "D_6") (pintype "unspecified"))
    )
    (net (code "83") (name "VCC") (class "Default")
      (node (ref "H1") (pin "1") (pinfunction "1_1") (pintype "input"))
      (node (ref "SEG1") (pin "3") (pinfunction "V1_3") (pintype "unspecified"))
      (node (ref "SEG1") (pin "8") (pinfunction "V2_8") (pintype "unspecified"))
      (node (ref "SEG2") (pin "3") (pinfunction "V1_3") (pintype "unspecified"))
      (node (ref "SEG2") (pin "8") (pinfunction "V2_8") (pintype "unspecified"))
      (node (ref "SEG3") (pin "3") (pinfunction "V1_3") (pintype "unspecified"))
      (node (ref "SEG3") (pin "8") (pinfunction "V2_8") (pintype "unspecified"))
      (node (ref "SEG4") (pin "3") (pinfunction "V1_3") (pintype "unspecified"))
      (node (ref "SEG4") (pin "8") (pinfunction "V2_8") (pintype "unspecified"))
      (node (ref "U1") (pin "10") (pinfunction "ENT_10") (pintype "unspecified"))
      (node (ref "U1") (pin "16") (pinfunction "VCC_16") (pintype "unspecified"))
      (node (ref "U1") (pin "7") (pinfunction "ENP_7") (pintype "unspecified"))
      (node (ref "U1") (pin "9") (pinfunction "LOAD_9") (pintype "unspecified"))
      (node (ref "U11") (pin "14") (pinfunction "VDD_14") (pintype "unspecified"))
      (node (ref "U12") (pin "16") (pinfunction "VDD_16") (pintype "unspecified"))
      (node (ref "U12") (pin "6") (pinfunction "(A=B)IN_6") (pintype "unspecified"))
      (node (ref "U13") (pin "16") (pinfunction "VDD_16") (pintype "unspecified"))
      (node (ref "U14") (pin "16") (pinfunction "VDD_16") (pintype "unspecified"))
      (node (ref "U14") (pin "6") (pinfunction "(A=B)IN_6") (pintype "unspecified"))
      (node (ref "U15") (pin "16") (pinfunction "VDD_16") (pintype "unspecified"))
      (node (ref "U2") (pin "10") (pinfunction "ENT_10") (pintype "unspecified"))
      (node (ref "U2") (pin "16") (pinfunction "VCC_16") (pintype "unspecified"))
      (node (ref "U2") (pin "7") (pinfunction "ENP_7") (pintype "unspecified"))
      (node (ref "U2") (pin "9") (pinfunction "LOAD_9") (pintype "unspecified"))
      (node (ref "U3") (pin "10") (pinfunction "ENT_10") (pintype "unspecified"))
      (node (ref "U3") (pin "16") (pinfunction "VCC_16") (pintype "unspecified"))
      (node (ref "U3") (pin "7") (pinfunction "ENP_7") (pintype "unspecified"))
      (node (ref "U3") (pin "9") (pinfunction "LOAD_9") (pintype "unspecified"))
      (node (ref "U4") (pin "1") (pinfunction "CLR_1") (pintype "unspecified"))
      (node (ref "U4") (pin "10") (pinfunction "ENT_10") (pintype "unspecified"))
      (node (ref "U4") (pin "16") (pinfunction "VCC_16") (pintype "unspecified"))
      (node (ref "U4") (pin "7") (pinfunction "ENP_7") (pintype "unspecified"))
      (node (ref "U4") (pin "9") (pinfunction "LOAD_9") (pintype "unspecified"))
      (node (ref "U5") (pin "14") (pinfunction "VCC_14") (pintype "unspecified"))
      (node (ref "U6") (pin "14") (pinfunction "VCC_14") (pintype "unspecified"))
      (node (ref "YIMAU1") (pin "16") (pinfunction "VCC_16") (pintype "passive"))
      (node (ref "YIMAU1") (pin "3") (pinfunction "LT_3") (pintype "unspecified"))
      (node (ref "YIMAU1") (pin "4") (pinfunction "BIRBO_4") (pintype "bidirectional"))
      (node (ref "YIMAU1") (pin "5") (pinfunction "RBI_5") (pintype "unspecified"))
      (node (ref "YIMAU2") (pin "16") (pinfunction "VCC_16") (pintype "passive"))
      (node (ref "YIMAU2") (pin "3") (pinfunction "LT_3") (pintype "unspecified"))
      (node (ref "YIMAU2") (pin "4") (pinfunction "BIRBO_4") (pintype "bidirectional"))
      (node (ref "YIMAU2") (pin "5") (pinfunction "RBI_5") (pintype "unspecified"))
      (node (ref "YIMAU3") (pin "16") (pinfunction "VCC_16") (pintype "passive"))
      (node (ref "YIMAU3") (pin "3") (pinfunction "LT_3") (pintype "unspecified"))
      (node (ref "YIMAU3") (pin "4") (pinfunction "BIRBO_4") (pintype "bidirectional"))
      (node (ref "YIMAU3") (pin "5") (pinfunction "RBI_5") (pintype "unspecified"))
      (node (ref "YIMAU4") (pin "16") (pinfunction "VCC_16") (pintype "passive"))
      (node (ref "YIMAU4") (pin "3") (pinfunction "LT_3") (pintype "unspecified"))
      (node (ref "YIMAU4") (pin "4") (pinfunction "BIRBO_4") (pintype "bidirectional"))
      (node (ref "YIMAU4") (pin "5") (pinfunction "RBI_5") (pintype "unspecified"))
    )
    (net (code "84") (name "unconnected-(SEG1-DP-Pad5)") (class "Default")
      (node (ref "SEG1") (pin "5") (pinfunction "DP_5") (pintype "unspecified"))
    )
    (net (code "85") (name "unconnected-(SEG2-DP-Pad5)") (class "Default")
      (node (ref "SEG2") (pin "5") (pinfunction "DP_5") (pintype "unspecified"))
    )
    (net (code "86") (name "unconnected-(SEG3-DP-Pad5)") (class "Default")
      (node (ref "SEG3") (pin "5") (pinfunction "DP_5") (pintype "unspecified"))
    )
    (net (code "87") (name "unconnected-(SEG4-DP-Pad5)") (class "Default")
      (node (ref "SEG4") (pin "5") (pinfunction "DP_5") (pintype "unspecified"))
    )
    (net (code "88") (name "unconnected-(U1-A-Pad3)") (class "Default")
      (node (ref "U1") (pin "3") (pinfunction "A_3") (pintype "unspecified"))
    )
    (net (code "89") (name "unconnected-(U1-B-Pad4)") (class "Default")
      (node (ref "U1") (pin "4") (pinfunction "B_4") (pintype "unspecified"))
    )
    (net (code "90") (name "unconnected-(U1-C-Pad5)") (class "Default")
      (node (ref "U1") (pin "5") (pinfunction "C_5") (pintype "unspecified"))
    )
    (net (code "91") (name "unconnected-(U1-D-Pad6)") (class "Default")
      (node (ref "U1") (pin "6") (pinfunction "D_6") (pintype "unspecified"))
    )
    (net (code "92") (name "unconnected-(U1-RCO-Pad15)") (class "Default")
      (node (ref "U1") (pin "15") (pinfunction "RCO_15") (pintype "unspecified"))
    )
    (net (code "93") (name "unconnected-(U2-A-Pad3)") (class "Default")
      (node (ref "U2") (pin "3") (pinfunction "A_3") (pintype "unspecified"))
    )
    (net (code "94") (name "unconnected-(U2-B-Pad4)") (class "Default")
      (node (ref "U2") (pin "4") (pinfunction "B_4") (pintype "unspecified"))
    )
    (net (code "95") (name "unconnected-(U2-C-Pad5)") (class "Default")
      (node (ref "U2") (pin "5") (pinfunction "C_5") (pintype "unspecified"))
    )
    (net (code "96") (name "unconnected-(U2-D-Pad6)") (class "Default")
      (node (ref "U2") (pin "6") (pinfunction "D_6") (pintype "unspecified"))
    )
    (net (code "97") (name "unconnected-(U3-A-Pad3)") (class "Default")
      (node (ref "U3") (pin "3") (pinfunction "A_3") (pintype "unspecified"))
    )
    (net (code "98") (name "unconnected-(U3-B-Pad4)") (class "Default")
      (node (ref "U3") (pin "4") (pinfunction "B_4") (pintype "unspecified"))
    )
    (net (code "99") (name "unconnected-(U3-C-Pad5)") (class "Default")
      (node (ref "U3") (pin "5") (pinfunction "C_5") (pintype "unspecified"))
    )
    (net (code "100") (name "unconnected-(U3-D-Pad6)") (class "Default")
      (node (ref "U3") (pin "6") (pinfunction "D_6") (pintype "unspecified"))
    )
    (net (code "101") (name "unconnected-(U3-RCO-Pad15)") (class "Default")
      (node (ref "U3") (pin "15") (pinfunction "RCO_15") (pintype "unspecified"))
    )
    (net (code "102") (name "unconnected-(U4-A-Pad3)") (class "Default")
      (node (ref "U4") (pin "3") (pinfunction "A_3") (pintype "unspecified"))
    )
    (net (code "103") (name "unconnected-(U4-B-Pad4)") (class "Default")
      (node (ref "U4") (pin "4") (pinfunction "B_4") (pintype "unspecified"))
    )
    (net (code "104") (name "unconnected-(U4-C-Pad5)") (class "Default")
      (node (ref "U4") (pin "5") (pinfunction "C_5") (pintype "unspecified"))
    )
    (net (code "105") (name "unconnected-(U4-D-Pad6)") (class "Default")
      (node (ref "U4") (pin "6") (pinfunction "D_6") (pintype "unspecified"))
    )
    (net (code "106") (name "unconnected-(U5-2A-Pad4)") (class "Default")
      (node (ref "U5") (pin "4") (pinfunction "2A_4") (pintype "unspecified"))
    )
    (net (code "107") (name "unconnected-(U5-2B-Pad5)") (class "Default")
      (node (ref "U5") (pin "5") (pinfunction "2B_5") (pintype "unspecified"))
    )
    (net (code "108") (name "unconnected-(U5-2Y-Pad6)") (class "Default")
      (node (ref "U5") (pin "6") (pinfunction "2Y_6") (pintype "unspecified"))
    )
    (net (code "109") (name "unconnected-(U5-3A-Pad9)") (class "Default")
      (node (ref "U5") (pin "9") (pinfunction "3A_9") (pintype "unspecified"))
    )
    (net (code "110") (name "unconnected-(U5-3B-Pad10)") (class "Default")
      (node (ref "U5") (pin "10") (pinfunction "3B_10") (pintype "unspecified"))
    )
    (net (code "111") (name "unconnected-(U5-3Y-Pad8)") (class "Default")
      (node (ref "U5") (pin "8") (pinfunction "3Y_8") (pintype "unspecified"))
    )
    (net (code "112") (name "unconnected-(U6-2A-Pad3)") (class "Default")
      (node (ref "U6") (pin "3") (pinfunction "2A_3") (pintype "unspecified"))
    )
    (net (code "113") (name "unconnected-(U6-2Y-Pad4)") (class "Default")
      (node (ref "U6") (pin "4") (pinfunction "2Y_4") (pintype "unspecified"))
    )
    (net (code "114") (name "unconnected-(U6-4A-Pad9)") (class "Default")
      (node (ref "U6") (pin "9") (pinfunction "4A_9") (pintype "unspecified"))
    )
    (net (code "115") (name "unconnected-(U6-4Y-Pad8)") (class "Default")
      (node (ref "U6") (pin "8") (pinfunction "4Y_8") (pintype "unspecified"))
    )
    (net (code "116") (name "unconnected-(U6-5A-Pad11)") (class "Default")
      (node (ref "U6") (pin "11") (pinfunction "5A_11") (pintype "unspecified"))
    )
    (net (code "117") (name "unconnected-(U6-5Y-Pad10)") (class "Default")
      (node (ref "U6") (pin "10") (pinfunction "5Y_10") (pintype "unspecified"))
    )
    (net (code "118") (name "unconnected-(U6-6A-Pad13)") (class "Default")
      (node (ref "U6") (pin "13") (pinfunction "6A_13") (pintype "unspecified"))
    )
    (net (code "119") (name "unconnected-(U6-6Y-Pad12)") (class "Default")
      (node (ref "U6") (pin "12") (pinfunction "6Y_12") (pintype "unspecified"))
    )
    (net (code "120") (name "unconnected-(U11-A-Pad1)") (class "Default")
      (node (ref "U11") (pin "1") (pinfunction "A_1") (pintype "unspecified"))
    )
    (net (code "121") (name "unconnected-(U11-B-Pad2)") (class "Default")
      (node (ref "U11") (pin "2") (pinfunction "B_2") (pintype "unspecified"))
    )
    (net (code "122") (name "unconnected-(U11-C-Pad8)") (class "Default")
      (node (ref "U11") (pin "8") (pinfunction "C_8") (pintype "unspecified"))
    )
    (net (code "123") (name "unconnected-(U11-G-Pad13)") (class "Default")
      (node (ref "U11") (pin "13") (pinfunction "G_13") (pintype "unspecified"))
    )
    (net (code "124") (name "unconnected-(U11-H-Pad12)") (class "Default")
      (node (ref "U11") (pin "12") (pinfunction "H_12") (pintype "unspecified"))
    )
    (net (code "125") (name "unconnected-(U11-I-Pad11)") (class "Default")
      (node (ref "U11") (pin "11") (pinfunction "I_11") (pintype "unspecified"))
    )
    (net (code "126") (name "unconnected-(U11-J-Pad9)") (class "Default")
      (node (ref "U11") (pin "9") (pinfunction "J_9") (pintype "unspecified"))
    )
    (net (code "127") (name "unconnected-(U11-L-Pad10)") (class "Default")
      (node (ref "U11") (pin "10") (pinfunction "L_10") (pintype "unspecified"))
    )
    (net (code "128") (name "unconnected-(U13-(A<B)OUT-Pad12)") (class "Default")
      (node (ref "U13") (pin "12") (pinfunction "(A<B)OUT_12") (pintype "unspecified"))
    )
    (net (code "129") (name "unconnected-(U13-(A>B)OUT-Pad13)") (class "Default")
      (node (ref "U13") (pin "13") (pinfunction "(A>B)OUT_13") (pintype "unspecified"))
    )
    (net (code "130") (name "unconnected-(U15-(A<B)OUT-Pad12)") (class "Default")
      (node (ref "U15") (pin "12") (pinfunction "(A<B)OUT_12") (pintype "unspecified"))
    )
    (net (code "131") (name "unconnected-(U15-(A>B)OUT-Pad13)") (class "Default")
      (node (ref "U15") (pin "13") (pinfunction "(A>B)OUT_13") (pintype "unspecified"))
    )
  )
)
